# Sema_Napajanje_EUROBOT-2016.net
KiCad netlist of a schematic drawn in Altium Designer
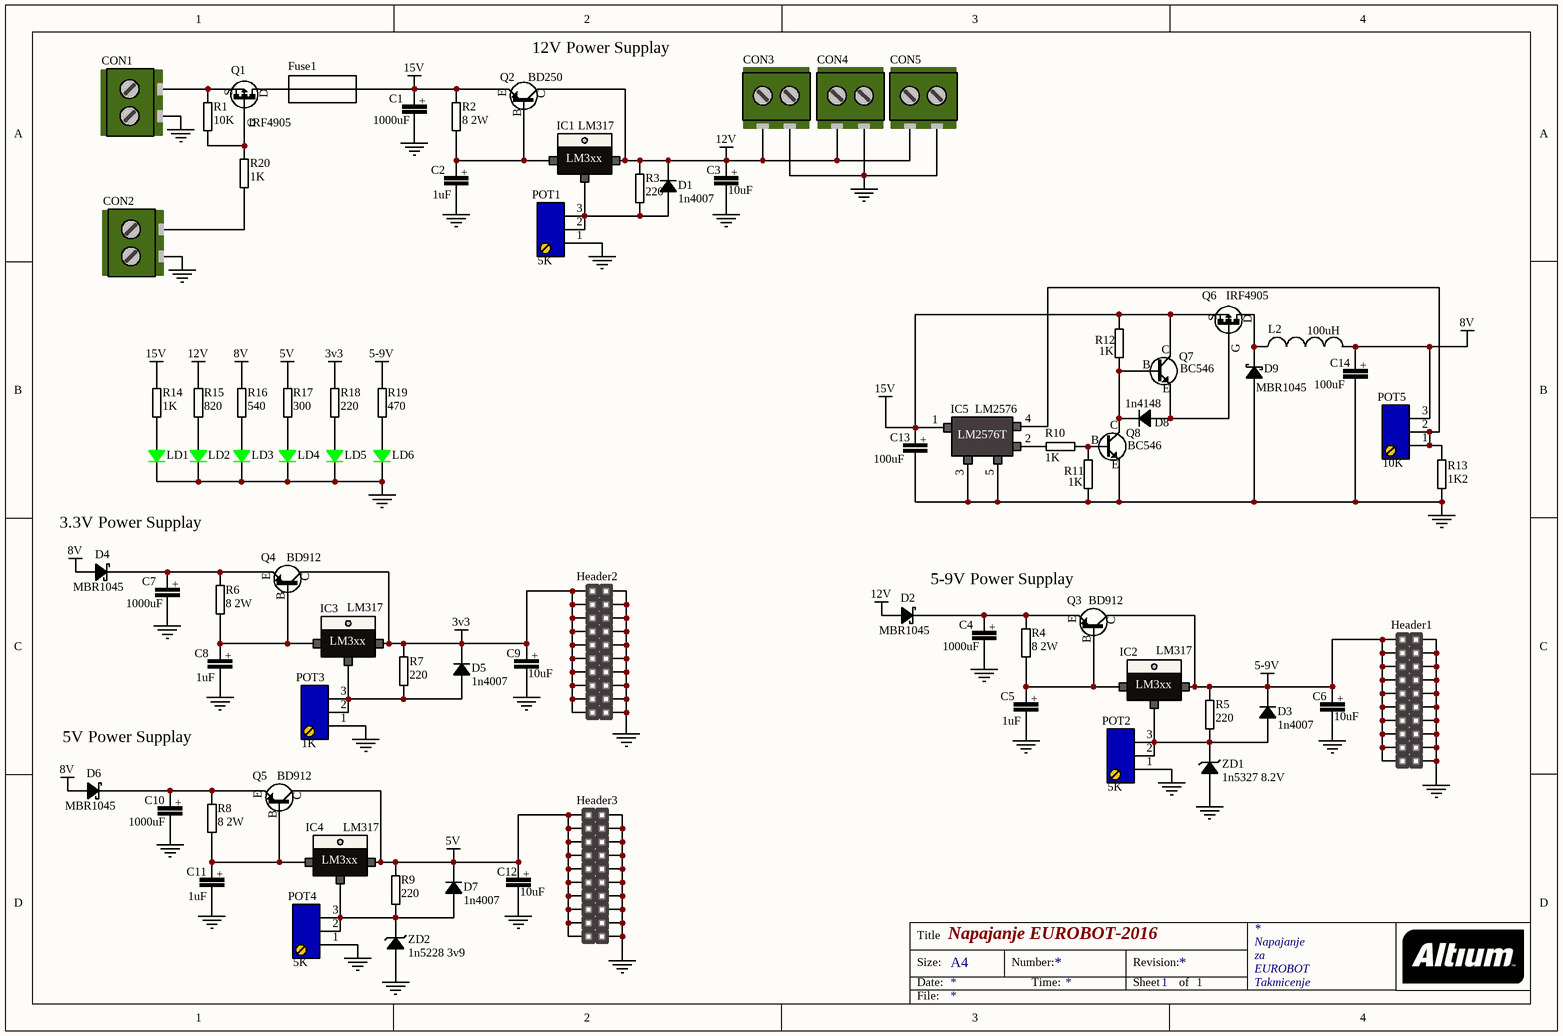
[diagram p0: Sema_Napajanje_EUROBOT-2016.SchDoc]

(export (version "E")
  (design (tool "Eeschema 10.0.6"))
  (components
    (comp (ref "C1")
      (value "1000uF")
      (footprint "C2(elektrolit)")
      (libsource (lib "KILEX LIB SCH") (part "C2"))
    )
    (comp (ref "C2") (value "1uF") (footprint "C1(ceramic)") (libsource (lib "KILEX LIB SCH") (part "C2")))
    (comp (ref "C3") (value "10uF") (footprint "C3") (libsource (lib "KILEX LIB SCH") (part "C2")))
    (comp (ref "C4")
      (value "1000uF")
      (footprint "C2(elektrolit)")
      (libsource (lib "KILEX LIB SCH") (part "C2"))
    )
    (comp (ref "C5") (value "1uF") (footprint "C2(elektrolit)") (libsource (lib "KILEX LIB SCH") (part "C2")))
    (comp (ref "C6") (value "10uF") (footprint "C3") (libsource (lib "KILEX LIB SCH") (part "C2")))
    (comp (ref "C7")
      (value "1000uF")
      (footprint "C2(elektrolit)")
      (libsource (lib "KILEX LIB SCH") (part "C2"))
    )
    (comp (ref "C8") (value "1uF") (footprint "C1(ceramic)") (libsource (lib "KILEX LIB SCH") (part "C2")))
    (comp (ref "C9") (value "10uF") (footprint "C3") (libsource (lib "KILEX LIB SCH") (part "C2")))
    (comp (ref "C10")
      (value "1000uF")
      (footprint "C2(elektrolit)")
      (libsource (lib "KILEX LIB SCH") (part "C2"))
    )
    (comp (ref "C11") (value "1uF") (footprint "C1(ceramic)") (libsource (lib "KILEX LIB SCH") (part "C2")))
    (comp (ref "C12") (value "10uF") (footprint "C3") (libsource (lib "KILEX LIB SCH") (part "C2")))
    (comp (ref "C13") (value "100uF") (footprint "C3") (libsource (lib "KILEX LIB SCH") (part "C2")))
    (comp (ref "C14") (value "100uF") (footprint "C3") (libsource (lib "KILEX LIB SCH") (part "C2")))
    (comp (ref "CON1") (value "Klema") (footprint "Klema") (libsource (lib "KILEX LIB SCH") (part "Klema")))
    (comp (ref "CON2") (value "Klema") (footprint "Klema") (libsource (lib "KILEX LIB SCH") (part "Klema")))
    (comp (ref "CON3") (value "Klema") (footprint "Klema") (libsource (lib "") (part "Klema_1")))
    (comp (ref "CON4") (value "Klema") (footprint "Klema") (libsource (lib "") (part "Klema_1")))
    (comp (ref "CON5") (value "Klema") (footprint "Klema") (libsource (lib "") (part "Klema_1")))
    (comp (ref "D1")
      (value "1n4007")
      (footprint "D1(300milsa)")
      (libsource (lib "KILEX LIB SCH") (part "D1"))
    )
    (comp (ref "D2")
      (value "MBR1045")
      (footprint "D2(TO220)")
      (libsource (lib "KILEX LIB SCH") (part "Sotki Diode"))
    )
    (comp (ref "D3")
      (value "1n4007")
      (footprint "D1(300milsa)")
      (libsource (lib "KILEX LIB SCH") (part "D1"))
    )
    (comp (ref "D4")
      (value "MBR1045")
      (footprint "D2(TO220)")
      (libsource (lib "KILEX LIB SCH") (part "Sotki Diode"))
    )
    (comp (ref "D5")
      (value "1n4007")
      (footprint "D1(300milsa)")
      (libsource (lib "KILEX LIB SCH") (part "D1"))
    )
    (comp (ref "D6")
      (value "MBR1045")
      (footprint "D2(TO220)")
      (libsource (lib "KILEX LIB SCH") (part "Sotki Diode"))
    )
    (comp (ref "D7")
      (value "1n4007")
      (footprint "D1(300milsa)")
      (libsource (lib "KILEX LIB SCH") (part "D1"))
    )
    (comp (ref "D8")
      (value "1n4148")
      (footprint "D1(300milsa)")
      (libsource (lib "KILEX LIB SCH") (part "D1"))
    )
    (comp (ref "D9")
      (value "MBR1045")
      (footprint "D2(TO220)")
      (libsource (lib "KILEX LIB SCH") (part "Sotki Diode"))
    )
    (comp (ref "Fuse1") (value "FUSE") (footprint "Osigurac") (libsource (lib "KILEX LIB SCH") (part "FUSE")))
    (comp (ref "Header1")
      (value "Header2x10")
      (footprint "HEADER2x10")
      (libsource (lib "KILEX LIB SCH") (part "Header2x10"))
    )
    (comp (ref "Header2")
      (value "Header2x10")
      (footprint "HEADER2x10")
      (libsource (lib "KILEX LIB SCH") (part "Header2x10"))
    )
    (comp (ref "Header3")
      (value "Header2x10")
      (footprint "HEADER2x10")
      (libsource (lib "KILEX LIB SCH") (part "Header2x10"))
    )
    (comp (ref "IC1")
      (value "LM317")
      (footprint "TO220")
      (libsource (lib "KILEX LIB SCH") (part "LM317/LM350"))
    )
    (comp (ref "IC2")
      (value "LM317")
      (footprint "TO220")
      (libsource (lib "KILEX LIB SCH") (part "LM317/LM350"))
    )
    (comp (ref "IC3")
      (value "LM317")
      (footprint "TO220")
      (libsource (lib "KILEX LIB SCH") (part "LM317/LM350"))
    )
    (comp (ref "IC4")
      (value "LM317")
      (footprint "TO220")
      (libsource (lib "KILEX LIB SCH") (part "LM317/LM350"))
    )
    (comp (ref "IC5") (value "LM2576") (footprint "LM2576") (libsource (lib "KILEX LIB SCH") (part "LM2576")))
    (comp (ref "L2") (value "100uH") (footprint "Kalem") (libsource (lib "KILEX LIB SCH") (part "Coil")))
    (comp (ref "LD1") (value "LED") (footprint "LED(3mm)") (libsource (lib "KILEX LIB SCH") (part "LED")))
    (comp (ref "LD2") (value "LED") (footprint "LED(3mm)") (libsource (lib "KILEX LIB SCH") (part "LED")))
    (comp (ref "LD3") (value "LED") (footprint "LED(3mm)") (libsource (lib "KILEX LIB SCH") (part "LED")))
    (comp (ref "LD4") (value "LED") (footprint "LED(3mm)") (libsource (lib "KILEX LIB SCH") (part "LED")))
    (comp (ref "LD5") (value "LED") (footprint "LED(3mm)") (libsource (lib "KILEX LIB SCH") (part "LED")))
    (comp (ref "LD6") (value "LED") (footprint "LED(3mm)") (libsource (lib "KILEX LIB SCH") (part "LED")))
    (comp (ref "POT1") (value "5K") (footprint "TRIM") (libsource (lib "KILEX LIB SCH") (part "TRIM")))
    (comp (ref "POT2") (value "5K") (footprint "TRIM") (libsource (lib "KILEX LIB SCH") (part "TRIM")))
    (comp (ref "POT3") (value "1K") (footprint "TRIM") (libsource (lib "KILEX LIB SCH") (part "TRIM")))
    (comp (ref "POT4") (value "5K") (footprint "TRIM") (libsource (lib "KILEX LIB SCH") (part "TRIM")))
    (comp (ref "POT5") (value "10K") (footprint "TRIM") (libsource (lib "KILEX LIB SCH") (part "TRIM")))
    (comp (ref "Q1")
      (value "IRF4905")
      (footprint "TO220")
      (libsource (lib "KILEX LIB SCH") (part "P-Channel MOSFET"))
    )
    (comp (ref "Q2")
      (value "BD250")
      (footprint "TO218")
      (libsource (lib "KILEX LIB SCH") (part "Transistor PNP"))
    )
    (comp (ref "Q3")
      (value "BD912")
      (footprint "TO220")
      (libsource (lib "KILEX LIB SCH") (part "Transistor PNP"))
    )
    (comp (ref "Q4")
      (value "BD912")
      (footprint "TO220")
      (libsource (lib "KILEX LIB SCH") (part "Transistor PNP"))
    )
    (comp (ref "Q5")
      (value "BD912")
      (footprint "TO220")
      (libsource (lib "KILEX LIB SCH") (part "Transistor PNP"))
    )
    (comp (ref "Q6")
      (value "IRF4905")
      (footprint "TO220")
      (libsource (lib "KILEX LIB SCH") (part "P-Channel MOSFET"))
    )
    (comp (ref "Q7")
      (value "BC546")
      (footprint "BC327")
      (libsource (lib "KILEX LIB SCH") (part "Transistor NPN"))
    )
    (comp (ref "Q8")
      (value "BC546")
      (footprint "BC327")
      (libsource (lib "KILEX LIB SCH") (part "Transistor NPN"))
    )
    (comp (ref "R1") (value "10K") (footprint "R1(300milsa)") (libsource (lib "KILEX LIB SCH") (part "R1")))
    (comp (ref "R2") (value "8 2W") (footprint "R1(2W)") (libsource (lib "KILEX LIB SCH") (part "R1")))
    (comp (ref "R3") (value "220") (footprint "R1(300milsa)") (libsource (lib "KILEX LIB SCH") (part "R1")))
    (comp (ref "R4") (value "8 2W") (footprint "R1(2W)") (libsource (lib "KILEX LIB SCH") (part "R1")))
    (comp (ref "R5") (value "220") (footprint "R1(300milsa)") (libsource (lib "KILEX LIB SCH") (part "R1")))
    (comp (ref "R6") (value "8 2W") (footprint "R1(2W)") (libsource (lib "KILEX LIB SCH") (part "R1")))
    (comp (ref "R7") (value "220") (footprint "R1(300milsa)") (libsource (lib "KILEX LIB SCH") (part "R1")))
    (comp (ref "R8") (value "8 2W") (footprint "R1(2W)") (libsource (lib "KILEX LIB SCH") (part "R1")))
    (comp (ref "R9") (value "220") (footprint "R1(300milsa)") (libsource (lib "KILEX LIB SCH") (part "R1")))
    (comp (ref "R10") (value "1K") (footprint "R1(300milsa)") (libsource (lib "KILEX LIB SCH") (part "R1")))
    (comp (ref "R11") (value "1K") (footprint "R1(300milsa)") (libsource (lib "KILEX LIB SCH") (part "R1")))
    (comp (ref "R12") (value "1K") (footprint "R1(300milsa)") (libsource (lib "KILEX LIB SCH") (part "R1")))
    (comp (ref "R13") (value "1K2") (footprint "R1(300milsa)") (libsource (lib "KILEX LIB SCH") (part "R1")))
    (comp (ref "R14") (value "1K") (footprint "R1(300milsa)") (libsource (lib "KILEX LIB SCH") (part "R1")))
    (comp (ref "R15") (value "820") (footprint "R1(300milsa)") (libsource (lib "KILEX LIB SCH") (part "R1")))
    (comp (ref "R16") (value "540") (footprint "R1(300milsa)") (libsource (lib "KILEX LIB SCH") (part "R1")))
    (comp (ref "R17") (value "300") (footprint "R1(300milsa)") (libsource (lib "KILEX LIB SCH") (part "R1")))
    (comp (ref "R18") (value "220") (footprint "R1(300milsa)") (libsource (lib "KILEX LIB SCH") (part "R1")))
    (comp (ref "R19") (value "470") (footprint "R1(300milsa)") (libsource (lib "KILEX LIB SCH") (part "R1")))
    (comp (ref "R20") (value "1K") (footprint "R1(300milsa)") (libsource (lib "KILEX LIB SCH") (part "R1")))
    (comp (ref "ZD1")
      (value "1n5327 8.2V")
      (footprint "D1(300milsa)")
      (libsource (lib "KILEX LIB SCH") (part "ZD1"))
    )
    (comp (ref "ZD2")
      (value "1n5228 3v9")
      (footprint "D1(300milsa)")
      (libsource (lib "KILEX LIB SCH") (part "ZD1"))
    )
  )
  (nets
    (net (code "1") (name "3v3") (class "Default")
      (node (ref "C9") (pin "1") (pinfunction "1_1") (pintype "passive"))
      (node (ref "D5") (pin "2") (pinfunction "2_2") (pintype "passive"))
      (node (ref "Header2") (pin "1") (pinfunction "1_1") (pintype "passive"))
      (node (ref "Header2") (pin "11") (pinfunction "11_11") (pintype "passive"))
      (node (ref "Header2") (pin "13") (pinfunction "13_13") (pintype "passive"))
      (node (ref "Header2") (pin "15") (pinfunction "15_15") (pintype "passive"))
      (node (ref "Header2") (pin "17") (pinfunction "17_17") (pintype "passive"))
      (node (ref "Header2") (pin "19") (pinfunction "19_19") (pintype "passive"))
      (node (ref "Header2") (pin "3") (pinfunction "3_3") (pintype "passive"))
      (node (ref "Header2") (pin "5") (pinfunction "5_5") (pintype "passive"))
      (node (ref "Header2") (pin "7") (pinfunction "7_7") (pintype "passive"))
      (node (ref "Header2") (pin "9") (pinfunction "9_9") (pintype "passive"))
      (node (ref "IC3") (pin "2") (pinfunction "2_2") (pintype "passive"))
      (node (ref "Q4") (pin "3") (pinfunction "3_3") (pintype "passive"))
      (node (ref "R18") (pin "1") (pinfunction "1_1") (pintype "passive"))
      (node (ref "R7") (pin "2") (pinfunction "2_2") (pintype "passive"))
    )
    (net (code "2") (name "5-9V") (class "Default")
      (node (ref "C6") (pin "1") (pinfunction "1_1") (pintype "passive"))
      (node (ref "D3") (pin "2") (pinfunction "2_2") (pintype "passive"))
      (node (ref "Header1") (pin "1") (pinfunction "1_1") (pintype "passive"))
      (node (ref "Header1") (pin "11") (pinfunction "11_11") (pintype "passive"))
      (node (ref "Header1") (pin "13") (pinfunction "13_13") (pintype "passive"))
      (node (ref "Header1") (pin "15") (pinfunction "15_15") (pintype "passive"))
      (node (ref "Header1") (pin "17") (pinfunction "17_17") (pintype "passive"))
      (node (ref "Header1") (pin "19") (pinfunction "19_19") (pintype "passive"))
      (node (ref "Header1") (pin "3") (pinfunction "3_3") (pintype "passive"))
      (node (ref "Header1") (pin "5") (pinfunction "5_5") (pintype "passive"))
      (node (ref "Header1") (pin "7") (pinfunction "7_7") (pintype "passive"))
      (node (ref "Header1") (pin "9") (pinfunction "9_9") (pintype "passive"))
      (node (ref "IC2") (pin "2") (pinfunction "2_2") (pintype "passive"))
      (node (ref "Q3") (pin "3") (pinfunction "3_3") (pintype "passive"))
      (node (ref "R19") (pin "1") (pinfunction "1_1") (pintype "passive"))
      (node (ref "R5") (pin "2") (pinfunction "2_2") (pintype "passive"))
    )
    (net (code "3") (name "5V") (class "Default")
      (node (ref "C12") (pin "1") (pinfunction "1_1") (pintype "passive"))
      (node (ref "D7") (pin "2") (pinfunction "2_2") (pintype "passive"))
      (node (ref "Header3") (pin "1") (pinfunction "1_1") (pintype "passive"))
      (node (ref "Header3") (pin "11") (pinfunction "11_11") (pintype "passive"))
      (node (ref "Header3") (pin "13") (pinfunction "13_13") (pintype "passive"))
      (node (ref "Header3") (pin "15") (pinfunction "15_15") (pintype "passive"))
      (node (ref "Header3") (pin "17") (pinfunction "17_17") (pintype "passive"))
      (node (ref "Header3") (pin "19") (pinfunction "19_19") (pintype "passive"))
      (node (ref "Header3") (pin "3") (pinfunction "3_3") (pintype "passive"))
      (node (ref "Header3") (pin "5") (pinfunction "5_5") (pintype "passive"))
      (node (ref "Header3") (pin "7") (pinfunction "7_7") (pintype "passive"))
      (node (ref "Header3") (pin "9") (pinfunction "9_9") (pintype "passive"))
      (node (ref "IC4") (pin "2") (pinfunction "2_2") (pintype "passive"))
      (node (ref "Q5") (pin "3") (pinfunction "3_3") (pintype "passive"))
      (node (ref "R17") (pin "1") (pinfunction "1_1") (pintype "passive"))
      (node (ref "R9") (pin "2") (pinfunction "2_2") (pintype "passive"))
    )
    (net (code "4") (name "8V") (class "Default")
      (node (ref "C14") (pin "1") (pinfunction "1_1") (pintype "passive"))
      (node (ref "D4") (pin "1") (pinfunction "1_1") (pintype "passive"))
      (node (ref "D6") (pin "1") (pinfunction "1_1") (pintype "passive"))
      (node (ref "L2") (pin "2") (pintype "passive"))
      (node (ref "POT5") (pin "3") (pinfunction "3_3") (pintype "passive"))
      (node (ref "R16") (pin "1") (pinfunction "1_1") (pintype "passive"))
    )
    (net (code "5") (name "12V") (class "Default")
      (node (ref "C3") (pin "1") (pinfunction "1_1") (pintype "passive"))
      (node (ref "CON3") (pin "1") (pinfunction "1_1") (pintype "passive"))
      (node (ref "CON4") (pin "1") (pinfunction "1_1") (pintype "passive"))
      (node (ref "CON5") (pin "1") (pinfunction "1_1") (pintype "passive"))
      (node (ref "D1") (pin "2") (pinfunction "2_2") (pintype "passive"))
      (node (ref "D2") (pin "1") (pinfunction "1_1") (pintype "passive"))
      (node (ref "IC1") (pin "2") (pinfunction "2_2") (pintype "passive"))
      (node (ref "Q2") (pin "3") (pinfunction "3_3") (pintype "passive"))
      (node (ref "R15") (pin "1") (pinfunction "1_1") (pintype "passive"))
      (node (ref "R3") (pin "2") (pinfunction "2_2") (pintype "passive"))
    )
    (net (code "6") (name "15V") (class "Default")
      (node (ref "C1") (pin "1") (pinfunction "1_1") (pintype "passive"))
      (node (ref "C13") (pin "1") (pinfunction "1_1") (pintype "passive"))
      (node (ref "Fuse1") (pin "2") (pinfunction "2_2") (pintype "passive"))
      (node (ref "IC5") (pin "1") (pinfunction "1_1") (pintype "passive"))
      (node (ref "Q2") (pin "2") (pinfunction "2_2") (pintype "passive"))
      (node (ref "Q6") (pin "3") (pinfunction "3_3") (pintype "passive"))
      (node (ref "Q7") (pin "2") (pinfunction "2_2") (pintype "passive"))
      (node (ref "R12") (pin "1") (pinfunction "1_1") (pintype "passive"))
      (node (ref "R14") (pin "1") (pinfunction "1_1") (pintype "passive"))
      (node (ref "R2") (pin "2") (pinfunction "2_2") (pintype "passive"))
    )
    (net (code "7") (name "GND") (class "Default")
      (node (ref "C1") (pin "2") (pinfunction "2_2") (pintype "passive"))
      (node (ref "C10") (pin "2") (pinfunction "2_2") (pintype "passive"))
      (node (ref "C11") (pin "2") (pinfunction "2_2") (pintype "passive"))
      (node (ref "C12") (pin "2") (pinfunction "2_2") (pintype "passive"))
      (node (ref "C13") (pin "2") (pinfunction "2_2") (pintype "passive"))
      (node (ref "C14") (pin "2") (pinfunction "2_2") (pintype "passive"))
      (node (ref "C2") (pin "2") (pinfunction "2_2") (pintype "passive"))
      (node (ref "C3") (pin "2") (pinfunction "2_2") (pintype "passive"))
      (node (ref "C4") (pin "2") (pinfunction "2_2") (pintype "passive"))
      (node (ref "C5") (pin "2") (pinfunction "2_2") (pintype "passive"))
      (node (ref "C6") (pin "2") (pinfunction "2_2") (pintype "passive"))
      (node (ref "C7") (pin "2") (pinfunction "2_2") (pintype "passive"))
      (node (ref "C8") (pin "2") (pinfunction "2_2") (pintype "passive"))
      (node (ref "C9") (pin "2") (pinfunction "2_2") (pintype "passive"))
      (node (ref "CON1") (pin "1") (pinfunction "1_1") (pintype "passive"))
      (node (ref "CON2") (pin "1") (pinfunction "1_1") (pintype "passive"))
      (node (ref "CON3") (pin "2") (pinfunction "2_2") (pintype "passive"))
      (node (ref "CON4") (pin "2") (pinfunction "2_2") (pintype "passive"))
      (node (ref "CON5") (pin "2") (pinfunction "2_2") (pintype "passive"))
      (node (ref "D9") (pin "1") (pinfunction "1_1") (pintype "passive"))
      (node (ref "Header1") (pin "10") (pinfunction "10_10") (pintype "passive"))
      (node (ref "Header1") (pin "12") (pinfunction "12_12") (pintype "passive"))
      (node (ref "Header1") (pin "14") (pinfunction "14_14") (pintype "passive"))
      (node (ref "Header1") (pin "16") (pinfunction "16_16") (pintype "passive"))
      (node (ref "Header1") (pin "18") (pinfunction "18_18") (pintype "passive"))
      (node (ref "Header1") (pin "2") (pinfunction "2_2") (pintype "passive"))
      (node (ref "Header1") (pin "20") (pinfunction "20_20") (pintype "passive"))
      (node (ref "Header1") (pin "4") (pinfunction "4_4") (pintype "passive"))
      (node (ref "Header1") (pin "6") (pinfunction "6_6") (pintype "passive"))
      (node (ref "Header1") (pin "8") (pinfunction "8_8") (pintype "passive"))
      (node (ref "Header2") (pin "10") (pinfunction "10_10") (pintype "passive"))
      (node (ref "Header2") (pin "12") (pinfunction "12_12") (pintype "passive"))
      (node (ref "Header2") (pin "14") (pinfunction "14_14") (pintype "passive"))
      (node (ref "Header2") (pin "16") (pinfunction "16_16") (pintype "passive"))
      (node (ref "Header2") (pin "18") (pinfunction "18_18") (pintype "passive"))
      (node (ref "Header2") (pin "2") (pinfunction "2_2") (pintype "passive"))
      (node (ref "Header2") (pin "20") (pinfunction "20_20") (pintype "passive"))
      (node (ref "Header2") (pin "4") (pinfunction "4_4") (pintype "passive"))
      (node (ref "Header2") (pin "6") (pinfunction "6_6") (pintype "passive"))
      (node (ref "Header2") (pin "8") (pinfunction "8_8") (pintype "passive"))
      (node (ref "Header3") (pin "10") (pinfunction "10_10") (pintype "passive"))
      (node (ref "Header3") (pin "12") (pinfunction "12_12") (pintype "passive"))
      (node (ref "Header3") (pin "14") (pinfunction "14_14") (pintype "passive"))
      (node (ref "Header3") (pin "16") (pinfunction "16_16") (pintype "passive"))
      (node (ref "Header3") (pin "18") (pinfunction "18_18") (pintype "passive"))
      (node (ref "Header3") (pin "2") (pinfunction "2_2") (pintype "passive"))
      (node (ref "Header3") (pin "20") (pinfunction "20_20") (pintype "passive"))
      (node (ref "Header3") (pin "4") (pinfunction "4_4") (pintype "passive"))
      (node (ref "Header3") (pin "6") (pinfunction "6_6") (pintype "passive"))
      (node (ref "Header3") (pin "8") (pinfunction "8_8") (pintype "passive"))
      (node (ref "IC5") (pin "3") (pinfunction "3_3") (pintype "passive"))
      (node (ref "IC5") (pin "5") (pinfunction "5_5") (pintype "passive"))
      (node (ref "LD1") (pin "2") (pinfunction "2_2") (pintype "passive"))
      (node (ref "LD2") (pin "2") (pinfunction "2_2") (pintype "passive"))
      (node (ref "LD3") (pin "2") (pinfunction "2_2") (pintype "passive"))
      (node (ref "LD4") (pin "2") (pinfunction "2_2") (pintype "passive"))
      (node (ref "LD5") (pin "2") (pinfunction "2_2") (pintype "passive"))
      (node (ref "LD6") (pin "2") (pinfunction "2_2") (pintype "passive"))
      (node (ref "POT1") (pin "1") (pinfunction "1_1") (pintype "passive"))
      (node (ref "POT2") (pin "1") (pinfunction "1_1") (pintype "passive"))
      (node (ref "POT3") (pin "1") (pinfunction "1_1") (pintype "passive"))
      (node (ref "POT4") (pin "1") (pinfunction "1_1") (pintype "passive"))
      (node (ref "Q8") (pin "3") (pinfunction "3_3") (pintype "passive"))
      (node (ref "R11") (pin "2") (pinfunction "2_2") (pintype "passive"))
      (node (ref "R13") (pin "2") (pinfunction "2_2") (pintype "passive"))
      (node (ref "ZD1") (pin "1") (pinfunction "1_1") (pintype "passive"))
      (node (ref "ZD2") (pin "1") (pinfunction "1_1") (pintype "passive"))
    )
    (net (code "8") (name "Net-(C2-Pad1)") (class "Default")
      (node (ref "C2") (pin "1") (pinfunction "1_1") (pintype "passive"))
      (node (ref "IC1") (pin "3") (pinfunction "3_3") (pintype "passive"))
      (node (ref "Q2") (pin "1") (pinfunction "1_1") (pintype "passive"))
      (node (ref "R2") (pin "1") (pinfunction "1_1") (pintype "passive"))
    )
    (net (code "9") (name "Net-(C4-Pad1)") (class "Default")
      (node (ref "C4") (pin "1") (pinfunction "1_1") (pintype "passive"))
      (node (ref "D2") (pin "2") (pinfunction "2_2") (pintype "passive"))
      (node (ref "Q3") (pin "2") (pinfunction "2_2") (pintype "passive"))
      (node (ref "R4") (pin "2") (pinfunction "2_2") (pintype "passive"))
    )
    (net (code "10") (name "Net-(C5-Pad1)") (class "Default")
      (node (ref "C5") (pin "1") (pinfunction "1_1") (pintype "passive"))
      (node (ref "IC2") (pin "3") (pinfunction "3_3") (pintype "passive"))
      (node (ref "Q3") (pin "1") (pinfunction "1_1") (pintype "passive"))
      (node (ref "R4") (pin "1") (pinfunction "1_1") (pintype "passive"))
    )
    (net (code "11") (name "Net-(C7-Pad1)") (class "Default")
      (node (ref "C7") (pin "1") (pinfunction "1_1") (pintype "passive"))
      (node (ref "D4") (pin "2") (pinfunction "2_2") (pintype "passive"))
      (node (ref "Q4") (pin "2") (pinfunction "2_2") (pintype "passive"))
      (node (ref "R6") (pin "2") (pinfunction "2_2") (pintype "passive"))
    )
    (net (code "12") (name "Net-(C8-Pad1)") (class "Default")
      (node (ref "C8") (pin "1") (pinfunction "1_1") (pintype "passive"))
      (node (ref "IC3") (pin "3") (pinfunction "3_3") (pintype "passive"))
      (node (ref "Q4") (pin "1") (pinfunction "1_1") (pintype "passive"))
      (node (ref "R6") (pin "1") (pinfunction "1_1") (pintype "passive"))
    )
    (net (code "13") (name "Net-(C10-Pad1)") (class "Default")
      (node (ref "C10") (pin "1") (pinfunction "1_1") (pintype "passive"))
      (node (ref "D6") (pin "2") (pinfunction "2_2") (pintype "passive"))
      (node (ref "Q5") (pin "2") (pinfunction "2_2") (pintype "passive"))
      (node (ref "R8") (pin "2") (pinfunction "2_2") (pintype "passive"))
    )
    (net (code "14") (name "Net-(C11-Pad1)") (class "Default")
      (node (ref "C11") (pin "1") (pinfunction "1_1") (pintype "passive"))
      (node (ref "IC4") (pin "3") (pinfunction "3_3") (pintype "passive"))
      (node (ref "Q5") (pin "1") (pinfunction "1_1") (pintype "passive"))
      (node (ref "R8") (pin "1") (pinfunction "1_1") (pintype "passive"))
    )
    (net (code "15") (name "Net-(CON1-Pad2)") (class "Default")
      (node (ref "CON1") (pin "2") (pinfunction "2_2") (pintype "passive"))
      (node (ref "Q1") (pin "3") (pinfunction "3_3") (pintype "passive"))
      (node (ref "R1") (pin "2") (pinfunction "2_2") (pintype "passive"))
    )
    (net (code "16") (name "Net-(CON2-Pad2)") (class "Default")
      (node (ref "CON2") (pin "2") (pinfunction "2_2") (pintype "passive"))
      (node (ref "R20") (pin "1") (pinfunction "1_1") (pintype "passive"))
    )
    (net (code "17") (name "Net-(D1-Pad1)") (class "Default")
      (node (ref "D1") (pin "1") (pinfunction "1_1") (pintype "passive"))
      (node (ref "IC1") (pin "1") (pinfunction "1_1") (pintype "passive"))
      (node (ref "POT1") (pin "2") (pinfunction "2_2") (pintype "passive"))
      (node (ref "POT1") (pin "3") (pinfunction "3_3") (pintype "passive"))
      (node (ref "R3") (pin "1") (pinfunction "1_1") (pintype "passive"))
    )
    (net (code "18") (name "Net-(D3-Pad1)") (class "Default")
      (node (ref "D3") (pin "1") (pinfunction "1_1") (pintype "passive"))
      (node (ref "IC2") (pin "1") (pinfunction "1_1") (pintype "passive"))
      (node (ref "POT2") (pin "2") (pinfunction "2_2") (pintype "passive"))
      (node (ref "POT2") (pin "3") (pinfunction "3_3") (pintype "passive"))
      (node (ref "R5") (pin "1") (pinfunction "1_1") (pintype "passive"))
      (node (ref "ZD1") (pin "2") (pinfunction "2_2") (pintype "passive"))
    )
    (net (code "19") (name "Net-(D5-Pad1)") (class "Default")
      (node (ref "D5") (pin "1") (pinfunction "1_1") (pintype "passive"))
      (node (ref "IC3") (pin "1") (pinfunction "1_1") (pintype "passive"))
      (node (ref "POT3") (pin "2") (pinfunction "2_2") (pintype "passive"))
      (node (ref "POT3") (pin "3") (pinfunction "3_3") (pintype "passive"))
      (node (ref "R7") (pin "1") (pinfunction "1_1") (pintype "passive"))
    )
    (net (code "20") (name "Net-(D7-Pad1)") (class "Default")
      (node (ref "D7") (pin "1") (pinfunction "1_1") (pintype "passive"))
      (node (ref "IC4") (pin "1") (pinfunction "1_1") (pintype "passive"))
      (node (ref "POT4") (pin "2") (pinfunction "2_2") (pintype "passive"))
      (node (ref "POT4") (pin "3") (pinfunction "3_3") (pintype "passive"))
      (node (ref "R9") (pin "1") (pinfunction "1_1") (pintype "passive"))
      (node (ref "ZD2") (pin "2") (pinfunction "2_2") (pintype "passive"))
    )
    (net (code "21") (name "Net-(D8-Pad1)") (class "Default")
      (node (ref "D8") (pin "1") (pinfunction "1_1") (pintype "passive"))
      (node (ref "Q6") (pin "1") (pinfunction "1_1") (pintype "passive"))
      (node (ref "Q7") (pin "3") (pinfunction "3_3") (pintype "passive"))
    )
    (net (code "22") (name "Net-(D8-Pad2)") (class "Default")
      (node (ref "D8") (pin "2") (pinfunction "2_2") (pintype "passive"))
      (node (ref "Q7") (pin "1") (pinfunction "1_1") (pintype "passive"))
      (node (ref "Q8") (pin "2") (pinfunction "2_2") (pintype "passive"))
      (node (ref "R12") (pin "2") (pinfunction "2_2") (pintype "passive"))
    )
    (net (code "23") (name "Net-(D9-Pad2)") (class "Default")
      (node (ref "D9") (pin "2") (pinfunction "2_2") (pintype "passive"))
      (node (ref "L2") (pin "1") (pinfunction "1_1") (pintype "passive"))
      (node (ref "Q6") (pin "2") (pinfunction "2_2") (pintype "passive"))
    )
    (net (code "24") (name "Net-(Fuse1-Pad1)") (class "Default")
      (node (ref "Fuse1") (pin "1") (pinfunction "1_1") (pintype "passive"))
      (node (ref "Q1") (pin "2") (pinfunction "2_2") (pintype "passive"))
    )
    (net (code "25") (name "Net-(IC5-Pad2)") (class "Default")
      (node (ref "IC5") (pin "2") (pinfunction "2_2") (pintype "passive"))
      (node (ref "R10") (pin "2") (pinfunction "2_2") (pintype "passive"))
    )
    (net (code "26") (name "Net-(IC5-Pad4)") (class "Default")
      (node (ref "IC5") (pin "4") (pinfunction "4_4") (pintype "passive"))
      (node (ref "POT5") (pin "1") (pinfunction "1_1") (pintype "passive"))
      (node (ref "POT5") (pin "2") (pinfunction "2_2") (pintype "passive"))
      (node (ref "R13") (pin "1") (pinfunction "1_1") (pintype "passive"))
    )
    (net (code "27") (name "Net-(LD1-Pad1)") (class "Default")
      (node (ref "LD1") (pin "1") (pinfunction "1_1") (pintype "passive"))
      (node (ref "R14") (pin "2") (pinfunction "2_2") (pintype "passive"))
    )
    (net (code "28") (name "Net-(LD2-Pad1)") (class "Default")
      (node (ref "LD2") (pin "1") (pinfunction "1_1") (pintype "passive"))
      (node (ref "R15") (pin "2") (pinfunction "2_2") (pintype "passive"))
    )
    (net (code "29") (name "Net-(LD3-Pad1)") (class "Default")
      (node (ref "LD3") (pin "1") (pinfunction "1_1") (pintype "passive"))
      (node (ref "R16") (pin "2") (pinfunction "2_2") (pintype "passive"))
    )
    (net (code "30") (name "Net-(LD4-Pad1)") (class "Default")
      (node (ref "LD4") (pin "1") (pinfunction "1_1") (pintype "passive"))
      (node (ref "R17") (pin "2") (pinfunction "2_2") (pintype "passive"))
    )
    (net (code "31") (name "Net-(LD5-Pad1)") (class "Default")
      (node (ref "LD5") (pin "1") (pinfunction "1_1") (pintype "passive"))
      (node (ref "R18") (pin "2") (pinfunction "2_2") (pintype "passive"))
    )
    (net (code "32") (name "Net-(LD6-Pad1)") (class "Default")
      (node (ref "LD6") (pin "1") (pinfunction "1_1") (pintype "passive"))
      (node (ref "R19") (pin "2") (pinfunction "2_2") (pintype "passive"))
    )
    (net (code "33") (name "Net-(Q1-Pad1)") (class "Default")
      (node (ref "Q1") (pin "1") (pinfunction "1_1") (pintype "passive"))
      (node (ref "R1") (pin "1") (pinfunction "1_1") (pintype "passive"))
      (node (ref "R20") (pin "2") (pinfunction "2_2") (pintype "passive"))
    )
    (net (code "34") (name "Net-(Q8-Pad1)") (class "Default")
      (node (ref "Q8") (pin "1") (pinfunction "1_1") (pintype "passive"))
      (node (ref "R10") (pin "1") (pinfunction "1_1") (pintype "passive"))
      (node (ref "R11") (pin "1") (pinfunction "1_1") (pintype "passive"))
    )
  )
)
